# PLmodule.net
KiCad netlist of a schematic drawn in Altium Designer
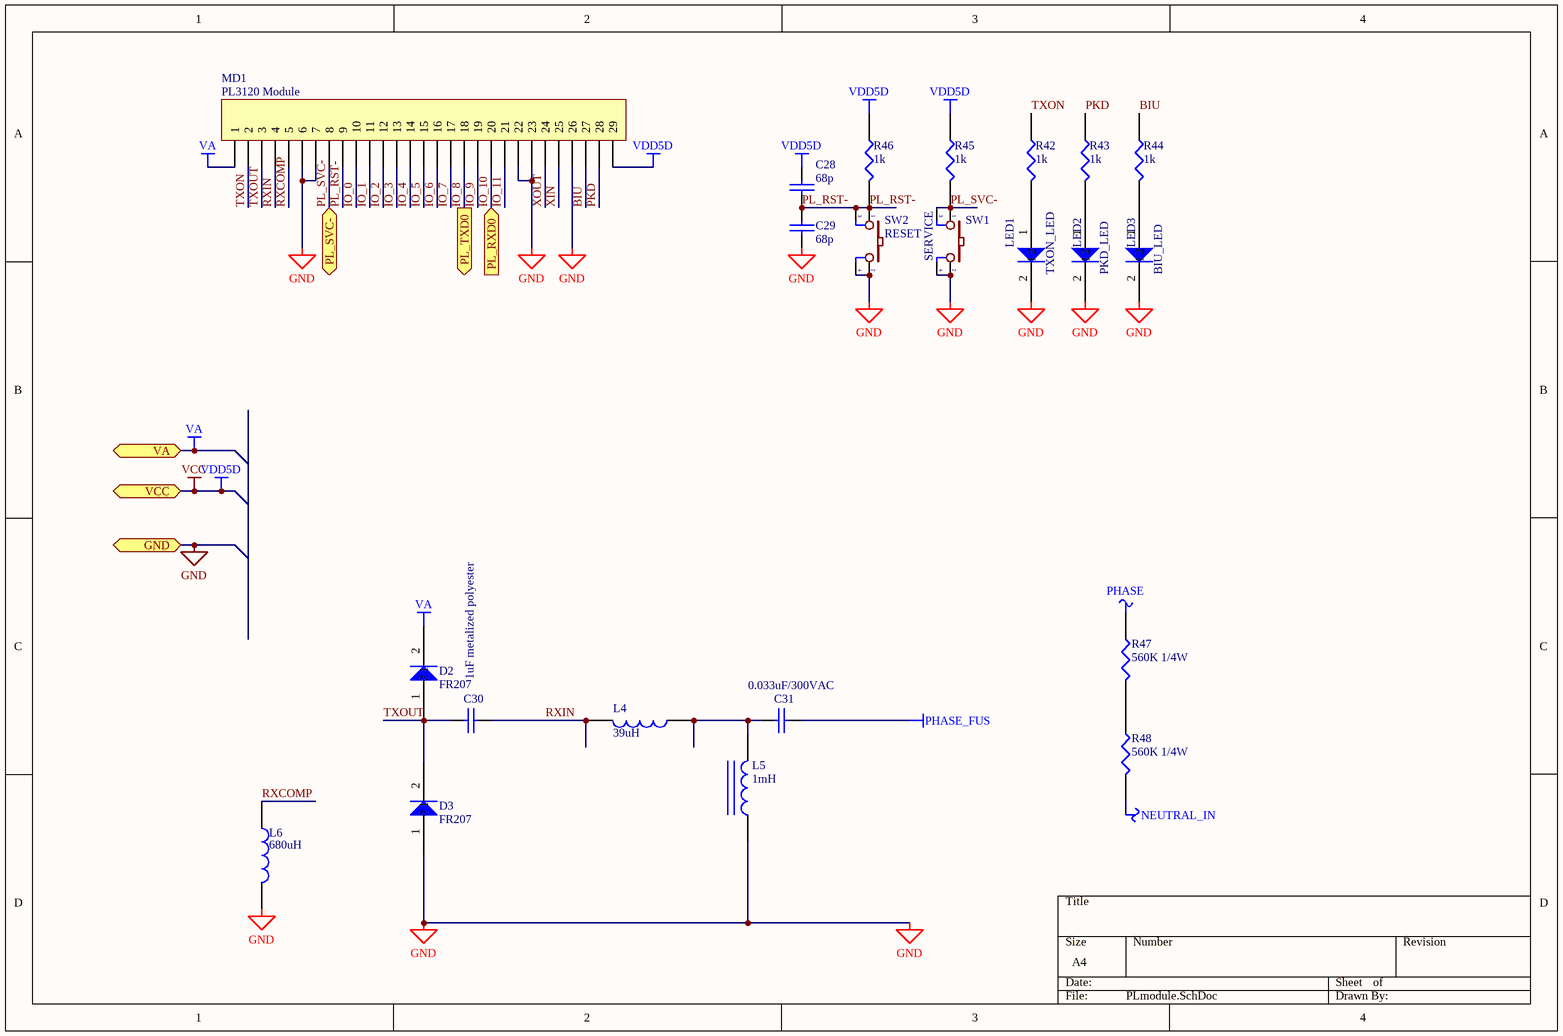
[diagram p0: PLmodule.SchDoc]

(export (version "E")
  (design (tool "Eeschema 10.0.6"))
  (components
    (comp (ref "C28")
      (value "68p")
      (footprint "6-0805_N")
      (description "Capacitor")
      (libsource (lib "*") (part "CAP"))
    )
    (comp (ref "C29")
      (value "68p")
      (footprint "6-0805_N")
      (description "Capacitor")
      (libsource (lib "*") (part "CAP"))
    )
    (comp (ref "C30")
      (value "1uF metalized polyester")
      (footprint "CSIP3")
      (description "Capacitor")
      (libsource (lib "*") (part "CAP"))
    )
    (comp (ref "C31")
      (value "0.033uF/300VAC")
      (footprint "100n400v")
      (description "Capacitor")
      (libsource (lib "*") (part "CAP"))
    )
    (comp (ref "D2") (value "FR207") (footprint "MELF-D5022-2009") (libsource (lib "*") (part "DIODE")))
    (comp (ref "D3") (value "FR207") (footprint "MELF-D5022-2009") (libsource (lib "*") (part "DIODE")))
    (comp (ref "L4") (value "39uH") (footprint "6D28") (libsource (lib "*") (part "INDUCTOR")))
    (comp (ref "L5") (value "1mH") (footprint "6-0805_N") (libsource (lib "*") (part "INDUCTOR IRON")))
    (comp (ref "L6") (value "680uH") (footprint "6-0805_N") (libsource (lib "") (part "INDUCTOR_1")))
    (comp (ref "LED1") (value "TXON_LED") (footprint "SMD _LED") (libsource (lib "*") (part "DIODE")))
    (comp (ref "LED2") (value "PKD_LED") (footprint "SMD _LED") (libsource (lib "*") (part "DIODE")))
    (comp (ref "LED3") (value "BIU_LED") (footprint "SMD _LED") (libsource (lib "*") (part "DIODE")))
    (comp (ref "MD1")
      (value "PL3120 Module")
      (footprint "ECHELONMODULE")
      (description "Connector")
      (libsource (lib "*") (part "CON29"))
    )
    (comp (ref "R42") (value "1k") (footprint "6-0805_N") (libsource (lib "*") (part "RES1")))
    (comp (ref "R43") (value "1k") (footprint "6-0805_N") (libsource (lib "*") (part "RES1")))
    (comp (ref "R44") (value "1k") (footprint "6-0805_N") (libsource (lib "*") (part "RES1")))
    (comp (ref "R45") (value "1k") (footprint "6-0805_N") (libsource (lib "*") (part "RES1")))
    (comp (ref "R46") (value "1k") (footprint "6-0805_N") (libsource (lib "*") (part "RES1")))
    (comp (ref "R47") (value "560K 1/4W") (footprint "3216[1206]") (libsource (lib "*") (part "RES1")))
    (comp (ref "R48") (value "560K 1/4W") (footprint "3216[1206]") (libsource (lib "*") (part "RES1")))
    (comp (ref "SW1")
      (value "SERVICE")
      (footprint "SW-4P-S")
      (description "Switch button 4 pin")
      (libsource (lib "syhaunguyen") (part "SW4-1"))
    )
    (comp (ref "SW2")
      (value "RESET")
      (footprint "SW-4P-S")
      (description "Switch button 4 pin")
      (libsource (lib "syhaunguyen") (part "SW4-1"))
    )
  )
  (nets
    (net (code "1") (name "/BIU") (class "Default")
      (node (ref "MD1") (pin "27") (pinfunction "27_27") (pintype "passive"))
      (node (ref "R44") (pin "1") (pinfunction "1_1") (pintype "passive"))
    )
    (net (code "2") (name "/IO_0") (class "Default")
      (node (ref "MD1") (pin "10") (pinfunction "10_10") (pintype "passive"))
    )
    (net (code "3") (name "/IO_1") (class "Default")
      (node (ref "MD1") (pin "11") (pinfunction "11_11") (pintype "passive"))
    )
    (net (code "4") (name "/IO_2") (class "Default")
      (node (ref "MD1") (pin "12") (pinfunction "12_12") (pintype "passive"))
    )
    (net (code "5") (name "/IO_3") (class "Default")
      (node (ref "MD1") (pin "13") (pinfunction "13_13") (pintype "passive"))
    )
    (net (code "6") (name "/IO_4") (class "Default")
      (node (ref "MD1") (pin "14") (pinfunction "14_14") (pintype "passive"))
    )
    (net (code "7") (name "/IO_5") (class "Default")
      (node (ref "MD1") (pin "15") (pinfunction "15_15") (pintype "passive"))
    )
    (net (code "8") (name "/IO_6") (class "Default")
      (node (ref "MD1") (pin "16") (pinfunction "16_16") (pintype "passive"))
    )
    (net (code "9") (name "/IO_7") (class "Default")
      (node (ref "MD1") (pin "17") (pinfunction "17_17") (pintype "passive"))
    )
    (net (code "10") (name "/IO_8") (class "Default")
      (node (ref "MD1") (pin "18") (pinfunction "18_18") (pintype "passive"))
    )
    (net (code "11") (name "/IO_9") (class "Default")
      (node (ref "MD1") (pin "19") (pinfunction "19_19") (pintype "passive"))
    )
    (net (code "12") (name "/IO_10") (class "Default")
      (node (ref "MD1") (pin "20") (pinfunction "20_20") (pintype "passive"))
    )
    (net (code "13") (name "/IO_11") (class "Default")
      (node (ref "MD1") (pin "21") (pinfunction "21_21") (pintype "passive"))
    )
    (net (code "14") (name "/PKD") (class "Default")
      (node (ref "MD1") (pin "28") (pinfunction "28_28") (pintype "passive"))
      (node (ref "R43") (pin "1") (pinfunction "1_1") (pintype "passive"))
    )
    (net (code "15") (name "/PL_RST-") (class "Default")
      (node (ref "C28") (pin "1") (pinfunction "1_1") (pintype "passive"))
      (node (ref "C29") (pin "1") (pinfunction "1_1") (pintype "passive"))
      (node (ref "MD1") (pin "9") (pinfunction "9_9") (pintype "passive"))
      (node (ref "R46") (pin "2") (pinfunction "2_2") (pintype "passive"))
      (node (ref "SW2") (pin "1") (pinfunction "1_1") (pintype "passive"))
      (node (ref "SW2") (pin "3") (pinfunction "3_3") (pintype "passive"))
    )
    (net (code "16") (name "/PL_SVC-") (class "Default")
      (node (ref "MD1") (pin "8") (pinfunction "8_8") (pintype "passive"))
      (node (ref "R45") (pin "2") (pinfunction "2_2") (pintype "passive"))
      (node (ref "SW1") (pin "1") (pinfunction "1_1") (pintype "passive"))
      (node (ref "SW1") (pin "3") (pinfunction "3_3") (pintype "passive"))
    )
    (net (code "17") (name "/RXCOMP") (class "Default")
      (node (ref "L6") (pin "1") (pinfunction "1_1") (pintype "passive"))
      (node (ref "MD1") (pin "5") (pinfunction "5_5") (pintype "passive"))
    )
    (net (code "18") (name "/RXIN") (class "Default")
      (node (ref "C30") (pin "2") (pinfunction "2_2") (pintype "passive"))
      (node (ref "L4") (pin "1") (pinfunction "1_1") (pintype "passive"))
      (node (ref "MD1") (pin "4") (pinfunction "4_4") (pintype "passive"))
    )
    (net (code "19") (name "/TXON") (class "Default")
      (node (ref "MD1") (pin "2") (pinfunction "2_2") (pintype "passive"))
      (node (ref "R42") (pin "1") (pinfunction "1_1") (pintype "passive"))
    )
    (net (code "20") (name "/TXOUT") (class "Default")
      (node (ref "C30") (pin "1") (pinfunction "1_1") (pintype "passive"))
      (node (ref "D2") (pin "1") (pinfunction "1_1") (pintype "passive"))
      (node (ref "D3") (pin "2") (pinfunction "2_2") (pintype "passive"))
      (node (ref "MD1") (pin "3") (pinfunction "3_3") (pintype "passive"))
    )
    (net (code "21") (name "/XIN") (class "Default")
      (node (ref "MD1") (pin "25") (pinfunction "25_25") (pintype "passive"))
    )
    (net (code "22") (name "/XOUT") (class "Default")
      (node (ref "MD1") (pin "24") (pinfunction "24_24") (pintype "passive"))
    )
    (net (code "23") (name "GND") (class "Default")
      (node (ref "C29") (pin "2") (pinfunction "2_2") (pintype "passive"))
      (node (ref "D3") (pin "1") (pinfunction "1_1") (pintype "passive"))
      (node (ref "L5") (pin "2") (pinfunction "2_2") (pintype "passive"))
      (node (ref "L6") (pin "2") (pinfunction "2_2") (pintype "passive"))
      (node (ref "LED1") (pin "2") (pinfunction "2_2") (pintype "passive"))
      (node (ref "LED2") (pin "2") (pinfunction "2_2") (pintype "passive"))
      (node (ref "LED3") (pin "2") (pinfunction "2_2") (pintype "passive"))
      (node (ref "MD1") (pin "22") (pinfunction "22_22") (pintype "passive"))
      (node (ref "MD1") (pin "23") (pinfunction "23_23") (pintype "passive"))
      (node (ref "MD1") (pin "26") (pinfunction "26_26") (pintype "passive"))
      (node (ref "MD1") (pin "6") (pinfunction "6_6") (pintype "passive"))
      (node (ref "MD1") (pin "7") (pinfunction "7_7") (pintype "passive"))
      (node (ref "SW1") (pin "2") (pinfunction "2_2") (pintype "passive"))
      (node (ref "SW1") (pin "4") (pinfunction "4_4") (pintype "passive"))
      (node (ref "SW2") (pin "2") (pinfunction "2_2") (pintype "passive"))
      (node (ref "SW2") (pin "4") (pinfunction "4_4") (pintype "passive"))
    )
    (net (code "24") (name "NEUTRAL_IN") (class "Default")
      (node (ref "R48") (pin "1") (pinfunction "1_1") (pintype "passive"))
    )
    (net (code "25") (name "Net-(C31-Pad2)") (class "Default")
      (node (ref "C31") (pin "2") (pinfunction "2_2") (pintype "passive"))
      (node (ref "L4") (pin "2") (pinfunction "2_2") (pintype "passive"))
      (node (ref "L5") (pin "1") (pinfunction "1_1") (pintype "passive"))
    )
    (net (code "26") (name "Net-(LED1-Pad1)") (class "Default")
      (node (ref "LED1") (pin "1") (pinfunction "1_1") (pintype "passive"))
      (node (ref "R42") (pin "2") (pinfunction "2_2") (pintype "passive"))
    )
    (net (code "27") (name "Net-(LED2-Pad1)") (class "Default")
      (node (ref "LED2") (pin "1") (pinfunction "1_1") (pintype "passive"))
      (node (ref "R43") (pin "2") (pinfunction "2_2") (pintype "passive"))
    )
    (net (code "28") (name "Net-(LED3-Pad1)") (class "Default")
      (node (ref "LED3") (pin "1") (pinfunction "1_1") (pintype "passive"))
      (node (ref "R44") (pin "2") (pinfunction "2_2") (pintype "passive"))
    )
    (net (code "29") (name "Net-(R47-Pad1)") (class "Default")
      (node (ref "R47") (pin "1") (pinfunction "1_1") (pintype "passive"))
      (node (ref "R48") (pin "2") (pinfunction "2_2") (pintype "passive"))
    )
    (net (code "30") (name "PHASE") (class "Default")
      (node (ref "R47") (pin "2") (pinfunction "2_2") (pintype "passive"))
    )
    (net (code "31") (name "PHASE_FUS") (class "Default")
      (node (ref "C31") (pin "1") (pinfunction "1_1") (pintype "passive"))
    )
    (net (code "32") (name "VA") (class "Default")
      (node (ref "D2") (pin "2") (pinfunction "2_2") (pintype "passive"))
      (node (ref "MD1") (pin "1") (pinfunction "1_1") (pintype "passive"))
    )
    (net (code "33") (name "VCC") (class "Default")
      (node (ref "C28") (pin "2") (pinfunction "2_2") (pintype "passive"))
      (node (ref "MD1") (pin "29") (pinfunction "29_29") (pintype "passive"))
      (node (ref "R45") (pin "1") (pinfunction "1_1") (pintype "passive"))
      (node (ref "R46") (pin "1") (pinfunction "1_1") (pintype "passive"))
    )
  )
)
